# dc26_maneki-neko_badge_VERSION2.net
KiCad netlist of a schematic drawn in EAGLE
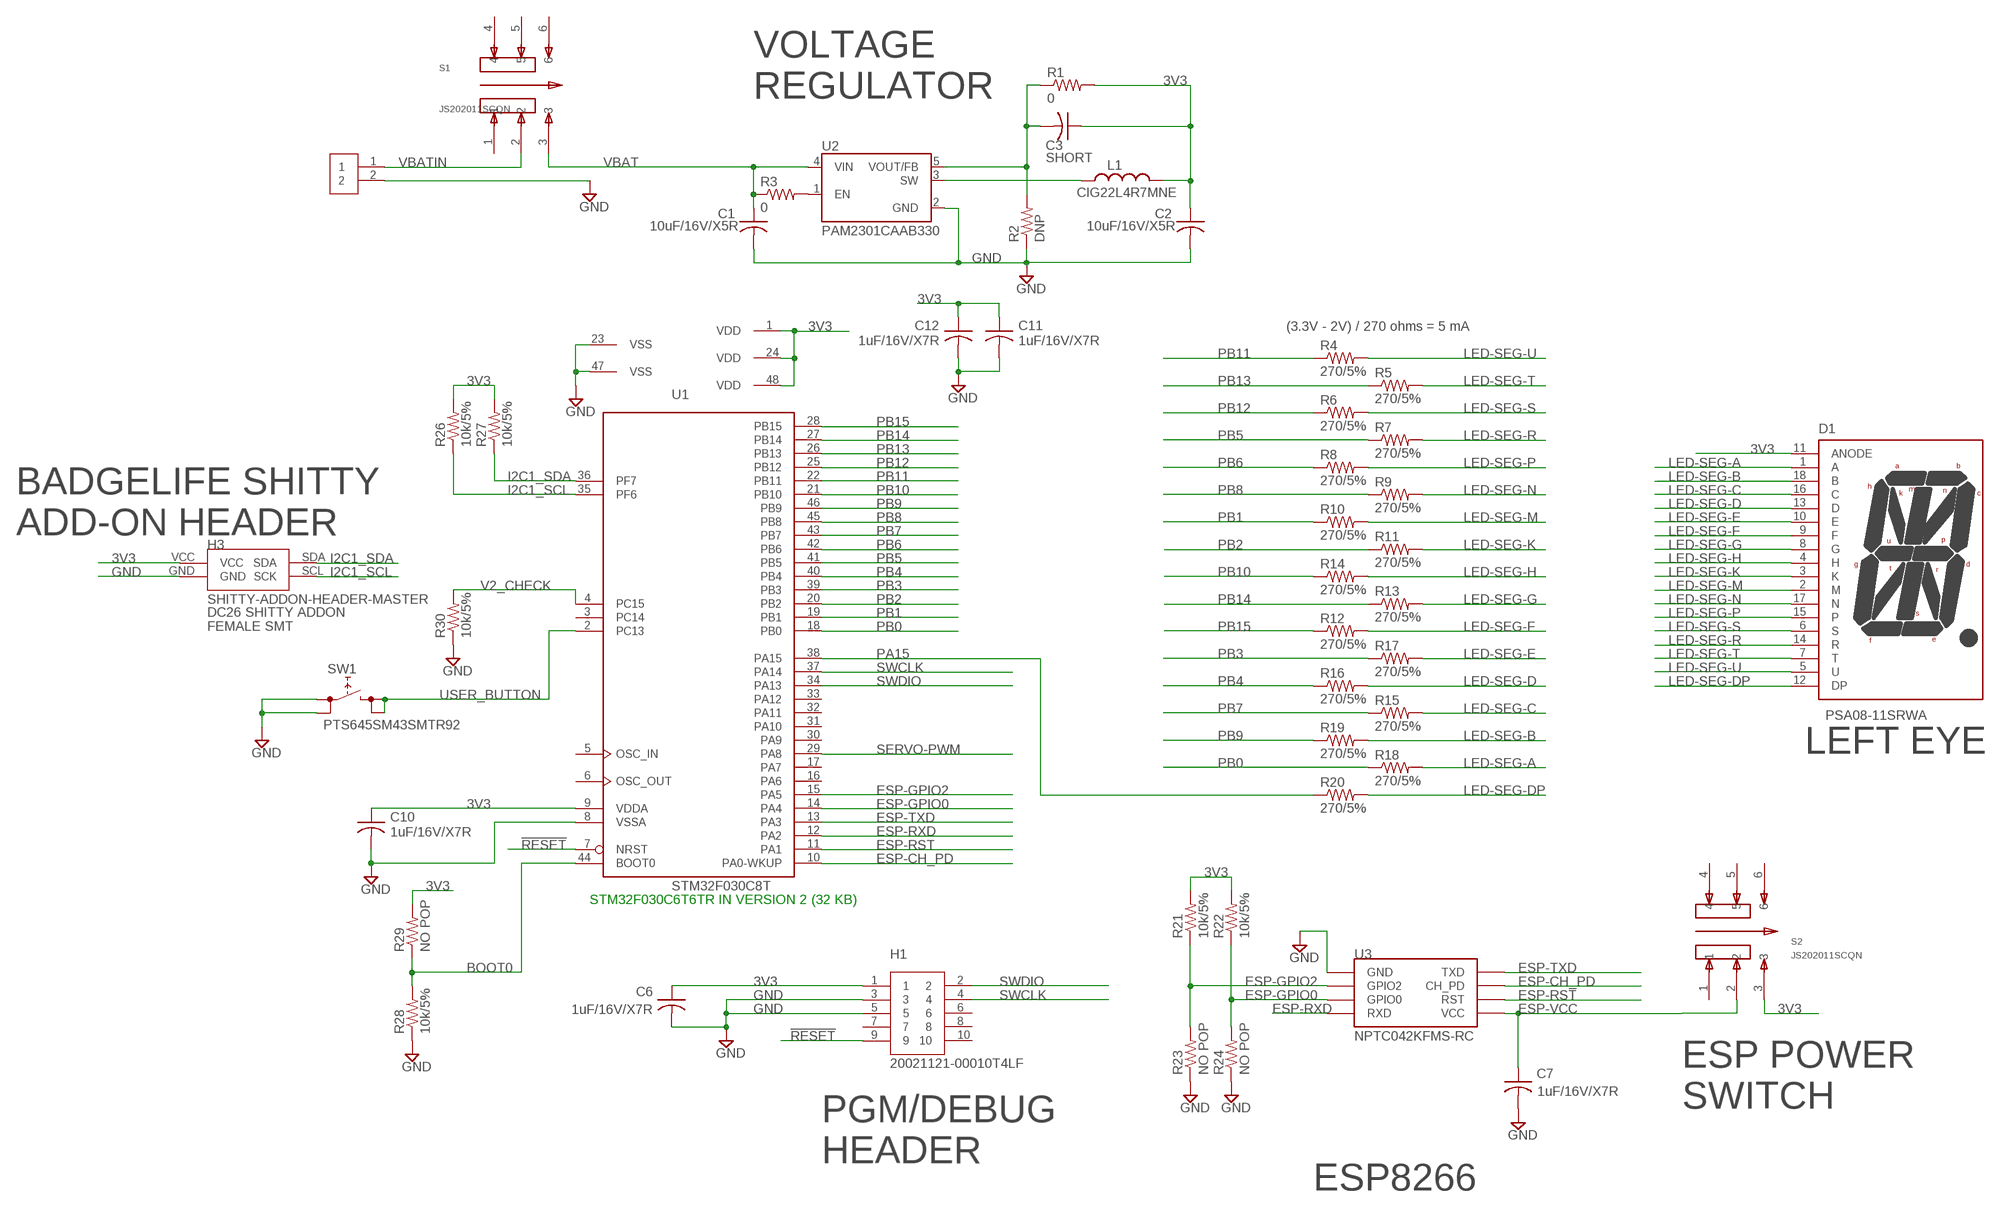
[diagram p0: schematic, sheet 1, part 1 of 2]
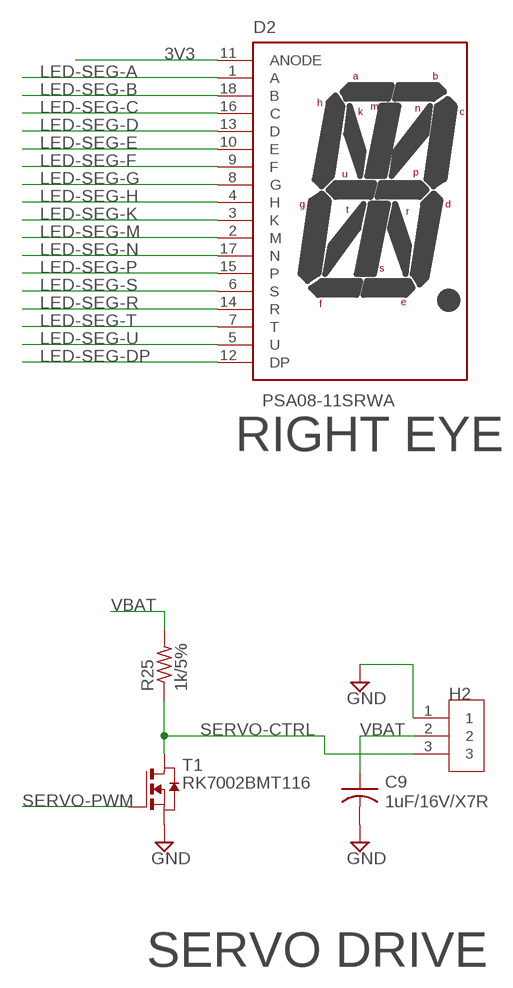
[diagram p1: schematic, sheet 1, part 2 of 2]

(export (version "E")
  (design (tool "Eeschema 10.0.6"))
  (components
    (comp (ref "C1")
      (value "10uF/16V/X5R")
      (footprint "eagle-import:C0805")
      (libsource (lib "eagle-import") (part "C-USC0805"))
    )
    (comp (ref "C2")
      (value "10uF/16V/X5R")
      (footprint "eagle-import:C0805")
      (libsource (lib "eagle-import") (part "C-USC0805"))
    )
    (comp (ref "C3")
      (value "SHORT")
      (footprint "eagle-import:C0805")
      (libsource (lib "eagle-import") (part "C-USC0805"))
    )
    (comp (ref "C6")
      (value "1uF/16V/X7R")
      (footprint "eagle-import:C0805")
      (libsource (lib "eagle-import") (part "C-USC0805"))
    )
    (comp (ref "C7")
      (value "1uF/16V/X7R")
      (footprint "eagle-import:C0805")
      (libsource (lib "eagle-import") (part "C-USC0805"))
    )
    (comp (ref "C9")
      (value "1uF/16V/X7R")
      (footprint "eagle-import:C0805")
      (libsource (lib "eagle-import") (part "C-USC0805"))
    )
    (comp (ref "C10")
      (value "1uF/16V/X7R")
      (footprint "eagle-import:C0805")
      (libsource (lib "eagle-import") (part "C-USC0805"))
    )
    (comp (ref "C11")
      (value "1uF/16V/X7R")
      (footprint "eagle-import:C0805")
      (libsource (lib "eagle-import") (part "C-USC0805"))
    )
    (comp (ref "C12")
      (value "1uF/16V/X7R")
      (footprint "eagle-import:C0805")
      (libsource (lib "eagle-import") (part "C-USC0805"))
    )
    (comp (ref "D1")
      (value "PSA08-11SRWA")
      (footprint "eagle-import:PSA08-11SRWA")
      (libsource (lib "eagle-import") (part "PSA08-11SRWA"))
    )
    (comp (ref "D2")
      (value "PSA08-11SRWA")
      (footprint "eagle-import:PSA08-11SRWA")
      (libsource (lib "eagle-import") (part "PSA08-11SRWA"))
    )
    (comp (ref "H1")
      (value "20021121-00010T4LF")
      (footprint "eagle-import:20021121-00010T4LF")
      (libsource (lib "eagle-import") (part "20021121-00010T4LF"))
    )
    (comp (ref "H2")
      (value "M20-8890345R")
      (footprint "eagle-import:M20-8890345R")
      (libsource (lib "eagle-import") (part "M20-8890345R"))
    )
    (comp (ref "H3")
      (value "SHITTY-ADDON-HEADER-MASTER")
      (footprint "eagle-import:2X2-0.1INCH-FEMALE-SMT")
      (libsource (lib "eagle-import") (part "SHITTY-ADDON-HEADER-MASTER"))
    )
    (comp (ref "H4")
      (value "BATTPADS-SMT")
      (footprint "eagle-import:BATTPADS-SMT")
      (libsource (lib "eagle-import") (part "BATTPADS-SMT"))
    )
    (comp (ref "L1")
      (value "CIG22L4R7MNE")
      (footprint "eagle-import:L-1008-US")
      (libsource (lib "eagle-import") (part "CIG22L4R7MNE"))
    )
    (comp (ref "R1")
      (value "0")
      (footprint "eagle-import:R0805")
      (libsource (lib "eagle-import") (part "R-US_R0805"))
    )
    (comp (ref "R2")
      (value "DNP")
      (footprint "eagle-import:R0805")
      (libsource (lib "eagle-import") (part "R-US_R0805"))
    )
    (comp (ref "R3")
      (value "0")
      (footprint "eagle-import:R0805")
      (libsource (lib "eagle-import") (part "R-US_R0805"))
    )
    (comp (ref "R4")
      (value "270/5%")
      (footprint "eagle-import:R0805")
      (libsource (lib "eagle-import") (part "R-US_R0805"))
    )
    (comp (ref "R5")
      (value "270/5%")
      (footprint "eagle-import:R0805")
      (libsource (lib "eagle-import") (part "R-US_R0805"))
    )
    (comp (ref "R6")
      (value "270/5%")
      (footprint "eagle-import:R0805")
      (libsource (lib "eagle-import") (part "R-US_R0805"))
    )
    (comp (ref "R7")
      (value "270/5%")
      (footprint "eagle-import:R0805")
      (libsource (lib "eagle-import") (part "R-US_R0805"))
    )
    (comp (ref "R8")
      (value "270/5%")
      (footprint "eagle-import:R0805")
      (libsource (lib "eagle-import") (part "R-US_R0805"))
    )
    (comp (ref "R9")
      (value "270/5%")
      (footprint "eagle-import:R0805")
      (libsource (lib "eagle-import") (part "R-US_R0805"))
    )
    (comp (ref "R10")
      (value "270/5%")
      (footprint "eagle-import:R0805")
      (libsource (lib "eagle-import") (part "R-US_R0805"))
    )
    (comp (ref "R11")
      (value "270/5%")
      (footprint "eagle-import:R0805")
      (libsource (lib "eagle-import") (part "R-US_R0805"))
    )
    (comp (ref "R12")
      (value "270/5%")
      (footprint "eagle-import:R0805")
      (libsource (lib "eagle-import") (part "R-US_R0805"))
    )
    (comp (ref "R13")
      (value "270/5%")
      (footprint "eagle-import:R0805")
      (libsource (lib "eagle-import") (part "R-US_R0805"))
    )
    (comp (ref "R14")
      (value "270/5%")
      (footprint "eagle-import:R0805")
      (libsource (lib "eagle-import") (part "R-US_R0805"))
    )
    (comp (ref "R15")
      (value "270/5%")
      (footprint "eagle-import:R0805")
      (libsource (lib "eagle-import") (part "R-US_R0805"))
    )
    (comp (ref "R16")
      (value "270/5%")
      (footprint "eagle-import:R0805")
      (libsource (lib "eagle-import") (part "R-US_R0805"))
    )
    (comp (ref "R17")
      (value "270/5%")
      (footprint "eagle-import:R0805")
      (libsource (lib "eagle-import") (part "R-US_R0805"))
    )
    (comp (ref "R18")
      (value "270/5%")
      (footprint "eagle-import:R0805")
      (libsource (lib "eagle-import") (part "R-US_R0805"))
    )
    (comp (ref "R19")
      (value "270/5%")
      (footprint "eagle-import:R0805")
      (libsource (lib "eagle-import") (part "R-US_R0805"))
    )
    (comp (ref "R20")
      (value "270/5%")
      (footprint "eagle-import:R0805")
      (libsource (lib "eagle-import") (part "R-US_R0805"))
    )
    (comp (ref "R21")
      (value "10k/5%")
      (footprint "eagle-import:R0805")
      (libsource (lib "eagle-import") (part "R-US_R0805"))
    )
    (comp (ref "R22")
      (value "10k/5%")
      (footprint "eagle-import:R0805")
      (libsource (lib "eagle-import") (part "R-US_R0805"))
    )
    (comp (ref "R23")
      (value "NO POP")
      (footprint "eagle-import:R0805")
      (libsource (lib "eagle-import") (part "R-US_R0805"))
    )
    (comp (ref "R24")
      (value "NO POP")
      (footprint "eagle-import:R0805")
      (libsource (lib "eagle-import") (part "R-US_R0805"))
    )
    (comp (ref "R25")
      (value "1k/5%")
      (footprint "eagle-import:R0805")
      (libsource (lib "eagle-import") (part "R-US_R0805"))
    )
    (comp (ref "R26")
      (value "10k/5%")
      (footprint "eagle-import:R0805")
      (libsource (lib "eagle-import") (part "R-US_R0805"))
    )
    (comp (ref "R27")
      (value "10k/5%")
      (footprint "eagle-import:R0805")
      (libsource (lib "eagle-import") (part "R-US_R0805"))
    )
    (comp (ref "R28")
      (value "10k/5%")
      (footprint "eagle-import:R0805")
      (libsource (lib "eagle-import") (part "R-US_R0805"))
    )
    (comp (ref "R29")
      (value "NO POP")
      (footprint "eagle-import:R0805")
      (libsource (lib "eagle-import") (part "R-US_R0805"))
    )
    (comp (ref "R30")
      (value "10k/5%")
      (footprint "eagle-import:R0805")
      (libsource (lib "eagle-import") (part "R-US_R0805"))
    )
    (comp (ref "S1")
      (value "JS202011SCQN")
      (footprint "eagle-import:SW_JS202011SCQN")
      (fields (field (name "MF") "C&K Components"))
      (libsource (lib "eagle-import") (part "JS202011SCQN"))
    )
    (comp (ref "S2")
      (value "JS202011SCQN")
      (footprint "eagle-import:SW_JS202011SCQN")
      (fields (field (name "MF") "C&K Components"))
      (libsource (lib "eagle-import") (part "JS202011SCQN"))
    )
    (comp (ref "SW1")
      (value "PTS645SM43SMTR92")
      (footprint "eagle-import:PTS645SM43SMTR92")
      (libsource (lib "eagle-import") (part "PTS645SM43SMTR92"))
    )
    (comp (ref "T1")
      (value "RK7002BMT116")
      (footprint "eagle-import:SOT-23")
      (libsource (lib "eagle-import") (part "NMOSSOT23"))
    )
    (comp (ref "U1")
      (value "STM32F030C8T")
      (footprint "eagle-import:LQFP48")
      (libsource (lib "eagle-import") (part "STM32F030CT8"))
    )
    (comp (ref "U2")
      (value "PAM2301CAAB330")
      (footprint "eagle-import:SOT95P280X100-5N")
      (libsource (lib "eagle-import") (part "PAM2301CAAB330"))
    )
    (comp (ref "U3")
      (value "NPTC042KFMS-RC")
      (footprint "eagle-import:NPTC042KFMS-RC")
      (libsource (lib "eagle-import") (part "NPTC042KFMS-RC"))
    )
  )
  (nets
    (net (code "1") (name "/3V3") (class "Default")
      (node (ref "C10") (pin "1") (pinfunction "1_1") (pintype "passive"))
      (node (ref "C11") (pin "1") (pinfunction "1_1") (pintype "passive"))
      (node (ref "C12") (pin "1") (pinfunction "1_1") (pintype "passive"))
      (node (ref "C2") (pin "1") (pinfunction "1_1") (pintype "passive"))
      (node (ref "C3") (pin "1") (pinfunction "1_1") (pintype "passive"))
      (node (ref "C6") (pin "1") (pinfunction "1_1") (pintype "passive"))
      (node (ref "D1") (pin "11") (pinfunction "ANODE_11") (pintype "bidirectional"))
      (node (ref "D2") (pin "11") (pinfunction "ANODE_11") (pintype "bidirectional"))
      (node (ref "H1") (pin "1") (pinfunction "1_1") (pintype "bidirectional"))
      (node (ref "H3") (pin "VCC") (pinfunction "VCC_VCC") (pintype "bidirectional"))
      (node (ref "L1") (pin "P$2") (pinfunction "2_P$2") (pintype "passive"))
      (node (ref "R1") (pin "2") (pinfunction "2_2") (pintype "passive"))
      (node (ref "R21") (pin "2") (pinfunction "2_2") (pintype "passive"))
      (node (ref "R22") (pin "2") (pinfunction "2_2") (pintype "passive"))
      (node (ref "R26") (pin "2") (pinfunction "2_2") (pintype "passive"))
      (node (ref "R27") (pin "2") (pinfunction "2_2") (pintype "passive"))
      (node (ref "R29") (pin "2") (pinfunction "2_2") (pintype "passive"))
      (node (ref "S2") (pin "3") (pinfunction "3_3") (pintype "passive"))
      (node (ref "U1") (pin "1") (pinfunction "VDD_1") (pintype "power_in"))
      (node (ref "U1") (pin "24") (pinfunction "VDD_24") (pintype "power_in"))
      (node (ref "U1") (pin "48") (pinfunction "VDD_48") (pintype "power_in"))
      (node (ref "U1") (pin "9") (pinfunction "VDDA_9") (pintype "power_in"))
    )
    (net (code "2") (name "/BOOT0") (class "Default")
      (node (ref "R28") (pin "2") (pinfunction "2_2") (pintype "passive"))
      (node (ref "R29") (pin "1") (pinfunction "1_1") (pintype "passive"))
      (node (ref "U1") (pin "44") (pinfunction "BOOT0_44") (pintype "input"))
    )
    (net (code "3") (name "/ESP-CH_PD") (class "Default")
      (node (ref "U1") (pin "10") (pinfunction "PA0-WKUP_10") (pintype "bidirectional"))
      (node (ref "U3") (pin "3") (pinfunction "CH_PD_3") (pintype "bidirectional"))
    )
    (net (code "4") (name "/ESP-GPIO0") (class "Default")
      (node (ref "R22") (pin "1") (pinfunction "1_1") (pintype "passive"))
      (node (ref "R24") (pin "2") (pinfunction "2_2") (pintype "passive"))
      (node (ref "U1") (pin "14") (pinfunction "PA4_14") (pintype "bidirectional"))
      (node (ref "U3") (pin "6") (pinfunction "GPIO0_6") (pintype "bidirectional"))
    )
    (net (code "5") (name "/ESP-GPIO2") (class "Default")
      (node (ref "R21") (pin "1") (pinfunction "1_1") (pintype "passive"))
      (node (ref "R23") (pin "2") (pinfunction "2_2") (pintype "passive"))
      (node (ref "U1") (pin "15") (pinfunction "PA5_15") (pintype "bidirectional"))
      (node (ref "U3") (pin "4") (pinfunction "GPIO2_4") (pintype "bidirectional"))
    )
    (net (code "6") (name "/ESP-RST") (class "Default")
      (node (ref "U1") (pin "11") (pinfunction "PA1_11") (pintype "bidirectional"))
      (node (ref "U3") (pin "5") (pinfunction "RST_5") (pintype "bidirectional"))
    )
    (net (code "7") (name "/ESP-RXD") (class "Default")
      (node (ref "U1") (pin "12") (pinfunction "PA2_12") (pintype "bidirectional"))
      (node (ref "U3") (pin "8") (pinfunction "RXD_8") (pintype "bidirectional"))
    )
    (net (code "8") (name "/ESP-TXD") (class "Default")
      (node (ref "U1") (pin "13") (pinfunction "PA3_13") (pintype "bidirectional"))
      (node (ref "U3") (pin "1") (pinfunction "TXD_1") (pintype "bidirectional"))
    )
    (net (code "9") (name "/ESP-VCC") (class "Default")
      (node (ref "C7") (pin "1") (pinfunction "1_1") (pintype "passive"))
      (node (ref "S2") (pin "2") (pinfunction "2_2") (pintype "passive"))
      (node (ref "U3") (pin "7") (pinfunction "VCC_7") (pintype "bidirectional"))
    )
    (net (code "10") (name "/I2C1_SCL") (class "Default")
      (node (ref "H3") (pin "SCL") (pinfunction "SCK_SCL") (pintype "bidirectional"))
      (node (ref "R26") (pin "1") (pinfunction "1_1") (pintype "passive"))
      (node (ref "U1") (pin "35") (pinfunction "PF6_35") (pintype "bidirectional"))
    )
    (net (code "11") (name "/I2C1_SDA") (class "Default")
      (node (ref "H3") (pin "SDA") (pinfunction "SDA_SDA") (pintype "bidirectional"))
      (node (ref "R27") (pin "1") (pinfunction "1_1") (pintype "passive"))
      (node (ref "U1") (pin "36") (pinfunction "PF7_36") (pintype "bidirectional"))
    )
    (net (code "12") (name "/LED-SEG-A") (class "Default")
      (node (ref "D1") (pin "1") (pinfunction "A_1") (pintype "bidirectional"))
      (node (ref "D2") (pin "1") (pinfunction "A_1") (pintype "bidirectional"))
      (node (ref "R18") (pin "2") (pinfunction "2_2") (pintype "passive"))
    )
    (net (code "13") (name "/LED-SEG-B") (class "Default")
      (node (ref "D1") (pin "18") (pinfunction "B_18") (pintype "bidirectional"))
      (node (ref "D2") (pin "18") (pinfunction "B_18") (pintype "bidirectional"))
      (node (ref "R19") (pin "2") (pinfunction "2_2") (pintype "passive"))
    )
    (net (code "14") (name "/LED-SEG-C") (class "Default")
      (node (ref "D1") (pin "16") (pinfunction "C_16") (pintype "bidirectional"))
      (node (ref "D2") (pin "16") (pinfunction "C_16") (pintype "bidirectional"))
      (node (ref "R15") (pin "2") (pinfunction "2_2") (pintype "passive"))
    )
    (net (code "15") (name "/LED-SEG-D") (class "Default")
      (node (ref "D1") (pin "13") (pinfunction "D_13") (pintype "bidirectional"))
      (node (ref "D2") (pin "13") (pinfunction "D_13") (pintype "bidirectional"))
      (node (ref "R16") (pin "2") (pinfunction "2_2") (pintype "passive"))
    )
    (net (code "16") (name "/LED-SEG-DP") (class "Default")
      (node (ref "D1") (pin "12") (pinfunction "DP_12") (pintype "bidirectional"))
      (node (ref "D2") (pin "12") (pinfunction "DP_12") (pintype "bidirectional"))
      (node (ref "R20") (pin "2") (pinfunction "2_2") (pintype "passive"))
    )
    (net (code "17") (name "/LED-SEG-E") (class "Default")
      (node (ref "D1") (pin "10") (pinfunction "E_10") (pintype "bidirectional"))
      (node (ref "D2") (pin "10") (pinfunction "E_10") (pintype "bidirectional"))
      (node (ref "R17") (pin "2") (pinfunction "2_2") (pintype "passive"))
    )
    (net (code "18") (name "/LED-SEG-F") (class "Default")
      (node (ref "D1") (pin "9") (pinfunction "F_9") (pintype "bidirectional"))
      (node (ref "D2") (pin "9") (pinfunction "F_9") (pintype "bidirectional"))
      (node (ref "R12") (pin "2") (pinfunction "2_2") (pintype "passive"))
    )
    (net (code "19") (name "/LED-SEG-G") (class "Default")
      (node (ref "D1") (pin "8") (pinfunction "G_8") (pintype "bidirectional"))
      (node (ref "D2") (pin "8") (pinfunction "G_8") (pintype "bidirectional"))
      (node (ref "R13") (pin "2") (pinfunction "2_2") (pintype "passive"))
    )
    (net (code "20") (name "/LED-SEG-H") (class "Default")
      (node (ref "D1") (pin "4") (pinfunction "H_4") (pintype "bidirectional"))
      (node (ref "D2") (pin "4") (pinfunction "H_4") (pintype "bidirectional"))
      (node (ref "R14") (pin "2") (pinfunction "2_2") (pintype "passive"))
    )
    (net (code "21") (name "/LED-SEG-K") (class "Default")
      (node (ref "D1") (pin "3") (pinfunction "K_3") (pintype "bidirectional"))
      (node (ref "D2") (pin "3") (pinfunction "K_3") (pintype "bidirectional"))
      (node (ref "R11") (pin "2") (pinfunction "2_2") (pintype "passive"))
    )
    (net (code "22") (name "/LED-SEG-M") (class "Default")
      (node (ref "D1") (pin "2") (pinfunction "M_2") (pintype "bidirectional"))
      (node (ref "D2") (pin "2") (pinfunction "M_2") (pintype "bidirectional"))
      (node (ref "R10") (pin "2") (pinfunction "2_2") (pintype "passive"))
    )
    (net (code "23") (name "/LED-SEG-N") (class "Default")
      (node (ref "D1") (pin "17") (pinfunction "N_17") (pintype "bidirectional"))
      (node (ref "D2") (pin "17") (pinfunction "N_17") (pintype "bidirectional"))
      (node (ref "R9") (pin "2") (pinfunction "2_2") (pintype "passive"))
    )
    (net (code "24") (name "/LED-SEG-P") (class "Default")
      (node (ref "D1") (pin "15") (pinfunction "P_15") (pintype "bidirectional"))
      (node (ref "D2") (pin "15") (pinfunction "P_15") (pintype "bidirectional"))
      (node (ref "R8") (pin "2") (pinfunction "2_2") (pintype "passive"))
    )
    (net (code "25") (name "/LED-SEG-R") (class "Default")
      (node (ref "D1") (pin "14") (pinfunction "R_14") (pintype "bidirectional"))
      (node (ref "D2") (pin "14") (pinfunction "R_14") (pintype "bidirectional"))
      (node (ref "R7") (pin "2") (pinfunction "2_2") (pintype "passive"))
    )
    (net (code "26") (name "/LED-SEG-S") (class "Default")
      (node (ref "D1") (pin "6") (pinfunction "S_6") (pintype "bidirectional"))
      (node (ref "D2") (pin "6") (pinfunction "S_6") (pintype "bidirectional"))
      (node (ref "R6") (pin "2") (pinfunction "2_2") (pintype "passive"))
    )
    (net (code "27") (name "/LED-SEG-T") (class "Default")
      (node (ref "D1") (pin "7") (pinfunction "T_7") (pintype "bidirectional"))
      (node (ref "D2") (pin "7") (pinfunction "T_7") (pintype "bidirectional"))
      (node (ref "R5") (pin "2") (pinfunction "2_2") (pintype "passive"))
    )
    (net (code "28") (name "/LED-SEG-U") (class "Default")
      (node (ref "D1") (pin "5") (pinfunction "U_5") (pintype "bidirectional"))
      (node (ref "D2") (pin "5") (pinfunction "U_5") (pintype "bidirectional"))
      (node (ref "R4") (pin "2") (pinfunction "2_2") (pintype "passive"))
    )
    (net (code "29") (name "/PA15") (class "Default")
      (node (ref "R20") (pin "1") (pinfunction "1_1") (pintype "passive"))
      (node (ref "U1") (pin "38") (pinfunction "PA15_38") (pintype "bidirectional"))
    )
    (net (code "30") (name "/PB0") (class "Default")
      (node (ref "R18") (pin "1") (pinfunction "1_1") (pintype "passive"))
      (node (ref "U1") (pin "18") (pinfunction "PB0_18") (pintype "bidirectional"))
    )
    (net (code "31") (name "/PB1") (class "Default")
      (node (ref "R10") (pin "1") (pinfunction "1_1") (pintype "passive"))
      (node (ref "U1") (pin "19") (pinfunction "PB1_19") (pintype "bidirectional"))
    )
    (net (code "32") (name "/PB2") (class "Default")
      (node (ref "R11") (pin "1") (pinfunction "1_1") (pintype "passive"))
      (node (ref "U1") (pin "20") (pinfunction "PB2_20") (pintype "bidirectional"))
    )
    (net (code "33") (name "/PB3") (class "Default")
      (node (ref "R17") (pin "1") (pinfunction "1_1") (pintype "passive"))
      (node (ref "U1") (pin "39") (pinfunction "PB3_39") (pintype "bidirectional"))
    )
    (net (code "34") (name "/PB4") (class "Default")
      (node (ref "R16") (pin "1") (pinfunction "1_1") (pintype "passive"))
      (node (ref "U1") (pin "40") (pinfunction "PB4_40") (pintype "bidirectional"))
    )
    (net (code "35") (name "/PB5") (class "Default")
      (node (ref "R7") (pin "1") (pinfunction "1_1") (pintype "passive"))
      (node (ref "U1") (pin "41") (pinfunction "PB5_41") (pintype "bidirectional"))
    )
    (net (code "36") (name "/PB6") (class "Default")
      (node (ref "R8") (pin "1") (pinfunction "1_1") (pintype "passive"))
      (node (ref "U1") (pin "42") (pinfunction "PB6_42") (pintype "bidirectional"))
    )
    (net (code "37") (name "/PB7") (class "Default")
      (node (ref "R15") (pin "1") (pinfunction "1_1") (pintype "passive"))
      (node (ref "U1") (pin "43") (pinfunction "PB7_43") (pintype "bidirectional"))
    )
    (net (code "38") (name "/PB8") (class "Default")
      (node (ref "R9") (pin "1") (pinfunction "1_1") (pintype "passive"))
      (node (ref "U1") (pin "45") (pinfunction "PB8_45") (pintype "bidirectional"))
    )
    (net (code "39") (name "/PB9") (class "Default")
      (node (ref "R19") (pin "1") (pinfunction "1_1") (pintype "passive"))
      (node (ref "U1") (pin "46") (pinfunction "PB9_46") (pintype "bidirectional"))
    )
    (net (code "40") (name "/PB10") (class "Default")
      (node (ref "R14") (pin "1") (pinfunction "1_1") (pintype "passive"))
      (node (ref "U1") (pin "21") (pinfunction "PB10_21") (pintype "bidirectional"))
    )
    (net (code "41") (name "/PB11") (class "Default")
      (node (ref "R4") (pin "1") (pinfunction "1_1") (pintype "passive"))
      (node (ref "U1") (pin "22") (pinfunction "PB11_22") (pintype "bidirectional"))
    )
    (net (code "42") (name "/PB12") (class "Default")
      (node (ref "R6") (pin "1") (pinfunction "1_1") (pintype "passive"))
      (node (ref "U1") (pin "25") (pinfunction "PB12_25") (pintype "bidirectional"))
    )
    (net (code "43") (name "/PB13") (class "Default")
      (node (ref "R5") (pin "1") (pinfunction "1_1") (pintype "passive"))
      (node (ref "U1") (pin "26") (pinfunction "PB13_26") (pintype "bidirectional"))
    )
    (net (code "44") (name "/PB14") (class "Default")
      (node (ref "R13") (pin "1") (pinfunction "1_1") (pintype "passive"))
      (node (ref "U1") (pin "27") (pinfunction "PB14_27") (pintype "bidirectional"))
    )
    (net (code "45") (name "/PB15") (class "Default")
      (node (ref "R12") (pin "1") (pinfunction "1_1") (pintype "passive"))
      (node (ref "U1") (pin "28") (pinfunction "PB15_28") (pintype "bidirectional"))
    )
    (net (code "46") (name "/SERVO-CTRL") (class "Default")
      (node (ref "H2") (pin "3") (pinfunction "3_3") (pintype "bidirectional"))
      (node (ref "R25") (pin "1") (pinfunction "1_1") (pintype "passive"))
      (node (ref "T1") (pin "1") (pinfunction "D_1") (pintype "passive"))
    )
    (net (code "47") (name "/SERVO-PWM") (class "Default")
      (node (ref "T1") (pin "3") (pinfunction "G_3") (pintype "passive"))
      (node (ref "U1") (pin "29") (pinfunction "PA8_29") (pintype "bidirectional"))
    )
    (net (code "48") (name "/SWCLK") (class "Default")
      (node (ref "H1") (pin "4") (pinfunction "4_4") (pintype "bidirectional"))
      (node (ref "U1") (pin "37") (pinfunction "PA14_37") (pintype "bidirectional"))
    )
    (net (code "49") (name "/SWDIO") (class "Default")
      (node (ref "H1") (pin "2") (pinfunction "2_2") (pintype "bidirectional"))
      (node (ref "U1") (pin "34") (pinfunction "PA13_34") (pintype "bidirectional"))
    )
    (net (code "50") (name "/USER_BUTTON") (class "Default")
      (node (ref "SW1") (pin "3") (pinfunction "1_3") (pintype "passive"))
      (node (ref "SW1") (pin "4") (pinfunction "1_4") (pintype "passive"))
      (node (ref "U1") (pin "2") (pinfunction "PC13_2") (pintype "bidirectional"))
    )
    (net (code "51") (name "/V2_CHECK") (class "Default")
      (node (ref "R30") (pin "2") (pinfunction "2_2") (pintype "passive"))
      (node (ref "U1") (pin "4") (pinfunction "PC15_4") (pintype "bidirectional"))
    )
    (net (code "52") (name "/VBAT") (class "Default")
      (node (ref "C1") (pin "1") (pinfunction "1_1") (pintype "passive"))
      (node (ref "C9") (pin "1") (pinfunction "1_1") (pintype "passive"))
      (node (ref "H2") (pin "2") (pinfunction "2_2") (pintype "bidirectional"))
      (node (ref "R25") (pin "2") (pinfunction "2_2") (pintype "passive"))
      (node (ref "R3") (pin "1") (pinfunction "1_1") (pintype "passive"))
      (node (ref "S1") (pin "3") (pinfunction "3_3") (pintype "passive"))
      (node (ref "U2") (pin "4") (pinfunction "VIN_4") (pintype "input"))
    )
    (net (code "53") (name "/VBATIN") (class "Default")
      (node (ref "H4") (pin "1") (pinfunction "1_1") (pintype "bidirectional"))
      (node (ref "S1") (pin "2") (pinfunction "2_2") (pintype "passive"))
    )
    (net (code "54") (name "/~{RESET}") (class "Default")
      (node (ref "H1") (pin "9") (pinfunction "9_9") (pintype "bidirectional"))
      (node (ref "U1") (pin "7") (pinfunction "NRST_7") (pintype "bidirectional"))
    )
    (net (code "55") (name "GND") (class "Default")
      (node (ref "C1") (pin "2") (pinfunction "2_2") (pintype "passive"))
      (node (ref "C10") (pin "2") (pinfunction "2_2") (pintype "passive"))
      (node (ref "C11") (pin "2") (pinfunction "2_2") (pintype "passive"))
      (node (ref "C12") (pin "2") (pinfunction "2_2") (pintype "passive"))
      (node (ref "C2") (pin "2") (pinfunction "2_2") (pintype "passive"))
      (node (ref "C6") (pin "2") (pinfunction "2_2") (pintype "passive"))
      (node (ref "C7") (pin "2") (pinfunction "2_2") (pintype "passive"))
      (node (ref "C9") (pin "2") (pinfunction "2_2") (pintype "passive"))
      (node (ref "H1") (pin "3") (pinfunction "3_3") (pintype "bidirectional"))
      (node (ref "H1") (pin "5") (pinfunction "5_5") (pintype "bidirectional"))
      (node (ref "H2") (pin "1") (pinfunction "1_1") (pintype "bidirectional"))
      (node (ref "H3") (pin "GND") (pinfunction "GND_GND") (pintype "bidirectional"))
      (node (ref "H4") (pin "2") (pinfunction "2_2") (pintype "bidirectional"))
      (node (ref "R2") (pin "1") (pinfunction "1_1") (pintype "passive"))
      (node (ref "R23") (pin "1") (pinfunction "1_1") (pintype "passive"))
      (node (ref "R24") (pin "1") (pinfunction "1_1") (pintype "passive"))
      (node (ref "R28") (pin "1") (pinfunction "1_1") (pintype "passive"))
      (node (ref "R30") (pin "1") (pinfunction "1_1") (pintype "passive"))
      (node (ref "SW1") (pin "1") (pinfunction "0_1") (pintype "passive"))
      (node (ref "SW1") (pin "2") (pinfunction "0_2") (pintype "passive"))
      (node (ref "T1") (pin "2") (pinfunction "S_2") (pintype "passive"))
      (node (ref "U1") (pin "23") (pinfunction "VSS_23") (pintype "power_in"))
      (node (ref "U1") (pin "47") (pinfunction "VSS_47") (pintype "power_in"))
      (node (ref "U1") (pin "8") (pinfunction "VSSA_8") (pintype "power_in"))
      (node (ref "U2") (pin "2") (pinfunction "GND_2") (pintype "power_in"))
      (node (ref "U3") (pin "2") (pinfunction "GND_2") (pintype "bidirectional"))
    )
    (net (code "56") (name "Net-(L1-1)") (class "Default")
      (node (ref "L1") (pin "P$1") (pinfunction "1_P$1") (pintype "passive"))
      (node (ref "U2") (pin "3") (pinfunction "SW_3") (pintype "output"))
    )
    (net (code "57") (name "Net-(U2-EN)") (class "Default")
      (node (ref "R3") (pin "2") (pinfunction "2_2") (pintype "passive"))
      (node (ref "U2") (pin "1") (pinfunction "EN_1") (pintype "input"))
    )
    (net (code "58") (name "Net-(U2-VOUT{slash}FB)") (class "Default")
      (node (ref "C3") (pin "2") (pinfunction "2_2") (pintype "passive"))
      (node (ref "R1") (pin "1") (pinfunction "1_1") (pintype "passive"))
      (node (ref "R2") (pin "2") (pinfunction "2_2") (pintype "passive"))
      (node (ref "U2") (pin "5") (pinfunction "VOUT/FB_5") (pintype "output"))
    )
    (net (code "59") (name "unconnected-(H1-Pad6)") (class "Default")
      (node (ref "H1") (pin "6") (pinfunction "6_6") (pintype "bidirectional"))
    )
    (net (code "60") (name "unconnected-(H1-Pad7)") (class "Default")
      (node (ref "H1") (pin "7") (pinfunction "7_7") (pintype "bidirectional"))
    )
    (net (code "61") (name "unconnected-(H1-Pad8)") (class "Default")
      (node (ref "H1") (pin "8") (pinfunction "8_8") (pintype "bidirectional"))
    )
    (net (code "62") (name "unconnected-(H1-Pad10)") (class "Default")
      (node (ref "H1") (pin "10") (pinfunction "10_10") (pintype "bidirectional"))
    )
    (net (code "63") (name "unconnected-(S1-Pad1)") (class "Default")
      (node (ref "S1") (pin "1") (pinfunction "1_1") (pintype "passive"))
    )
    (net (code "64") (name "unconnected-(S1-Pad4)") (class "Default")
      (node (ref "S1") (pin "4") (pinfunction "4_4") (pintype "passive"))
    )
    (net (code "65") (name "unconnected-(S1-Pad5)") (class "Default")
      (node (ref "S1") (pin "5") (pinfunction "5_5") (pintype "passive"))
    )
    (net (code "66") (name "unconnected-(S1-Pad6)") (class "Default")
      (node (ref "S1") (pin "6") (pinfunction "6_6") (pintype "passive"))
    )
    (net (code "67") (name "unconnected-(S2-Pad1)") (class "Default")
      (node (ref "S2") (pin "1") (pinfunction "1_1") (pintype "passive"))
    )
    (net (code "68") (name "unconnected-(S2-Pad4)") (class "Default")
      (node (ref "S2") (pin "4") (pinfunction "4_4") (pintype "passive"))
    )
    (net (code "69") (name "unconnected-(S2-Pad5)") (class "Default")
      (node (ref "S2") (pin "5") (pinfunction "5_5") (pintype "passive"))
    )
    (net (code "70") (name "unconnected-(S2-Pad6)") (class "Default")
      (node (ref "S2") (pin "6") (pinfunction "6_6") (pintype "passive"))
    )
    (net (code "71") (name "unconnected-(U1A-OSC_IN-Pad5)") (class "Default")
      (node (ref "U1") (pin "5") (pinfunction "OSC_IN_5") (pintype "bidirectional"))
    )
    (net (code "72") (name "unconnected-(U1A-OSC_OUT-Pad6)") (class "Default")
      (node (ref "U1") (pin "6") (pinfunction "OSC_OUT_6") (pintype "bidirectional"))
    )
    (net (code "73") (name "unconnected-(U1A-PA6-Pad16)") (class "Default")
      (node (ref "U1") (pin "16") (pinfunction "PA6_16") (pintype "bidirectional"))
    )
    (net (code "74") (name "unconnected-(U1A-PA7-Pad17)") (class "Default")
      (node (ref "U1") (pin "17") (pinfunction "PA7_17") (pintype "bidirectional"))
    )
    (net (code "75") (name "unconnected-(U1A-PA9-Pad30)") (class "Default")
      (node (ref "U1") (pin "30") (pinfunction "PA9_30") (pintype "bidirectional"))
    )
    (net (code "76") (name "unconnected-(U1A-PA10-Pad31)") (class "Default")
      (node (ref "U1") (pin "31") (pinfunction "PA10_31") (pintype "bidirectional"))
    )
    (net (code "77") (name "unconnected-(U1A-PA11-Pad32)") (class "Default")
      (node (ref "U1") (pin "32") (pinfunction "PA11_32") (pintype "bidirectional"))
    )
    (net (code "78") (name "unconnected-(U1A-PA12-Pad33)") (class "Default")
      (node (ref "U1") (pin "33") (pinfunction "PA12_33") (pintype "bidirectional"))
    )
    (net (code "79") (name "unconnected-(U1A-PC14-Pad3)") (class "Default")
      (node (ref "U1") (pin "3") (pinfunction "PC14_3") (pintype "bidirectional"))
    )
  )
)
